# Connectors.net
KiCad netlist of a schematic drawn in Altium Designer
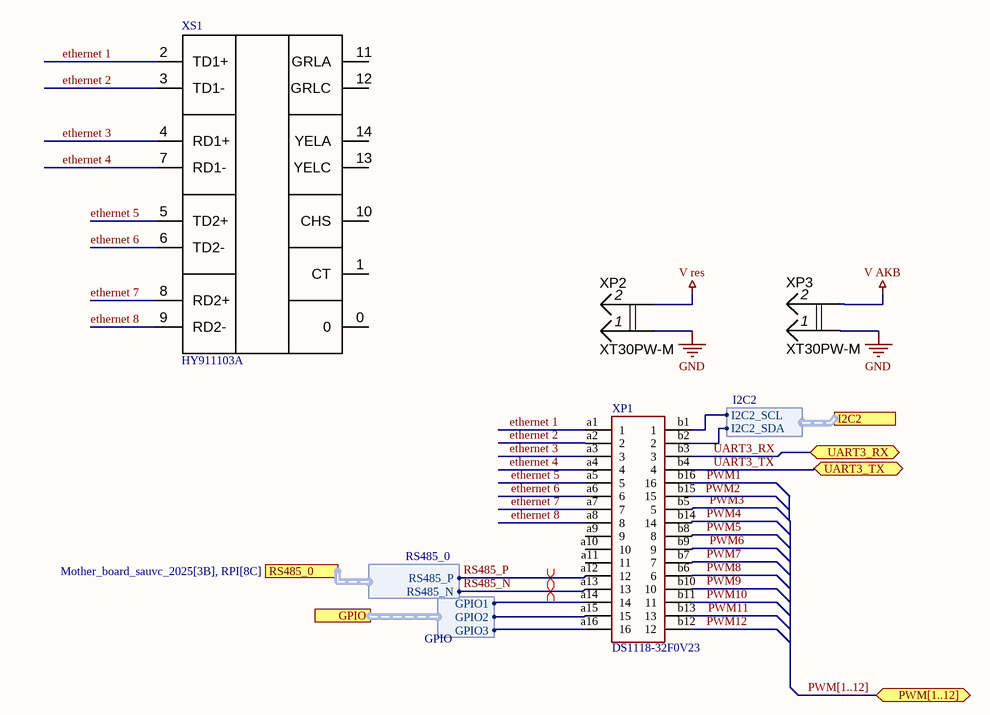
[diagram p0: Connectors.SchDoc]

(export (version "E")
  (design (tool "Eeschema 10.0.6"))
  (components
    (comp (ref "XP1")
      (value "DS1118-32F0V23")
      (footprint "DS1118-32M0R23")
      (libsource (lib "Schliba2") (part "DS1118-32F0V23"))
    )
    (comp (ref "XP2")
      (value "XT30PW-M")
      (footprint "XT30PW-M")
      (fields (field (name "MANUFACTURER") "AMASS") (field (name "PART NUMBER") "XT30PW-M"))
      (libsource (lib "Conectors") (part "XT30PW-M"))
    )
    (comp (ref "XP3")
      (value "XT30PW-M")
      (footprint "XT30PW-M")
      (fields (field (name "MANUFACTURER") "AMASS") (field (name "PART NUMBER") "XT30PW-M"))
      (libsource (lib "Conectors") (part "XT30PW-M"))
    )
    (comp (ref "XS1")
      (value "HY911103A")
      (footprint "HY911103A_HAN")
      (description "RG45")
      (fields (field (name "MANUFACTURER") "HanRun"))
      (libsource (lib "Conectors") (part "HY911103A"))
    )
  )
  (nets
    (net (code "4") (name "/GPIO1") (class "Default")
      (node (ref "XP1") (pin "a14") (pinfunction "14_a14") (pintype "passive"))
    )
    (net (code "5") (name "/GPIO2") (class "Default")
      (node (ref "XP1") (pin "a15") (pinfunction "15_a15") (pintype "passive"))
    )
    (net (code "6") (name "/GPIO3") (class "Default")
      (node (ref "XP1") (pin "a16") (pinfunction "16_a16") (pintype "passive"))
    )
    (net (code "7") (name "/I2C2_SCL") (class "Default")
      (node (ref "XP1") (pin "b1") (pinfunction "1_b1") (pintype "passive"))
    )
    (net (code "8") (name "/I2C2_SDA") (class "Default")
      (node (ref "XP1") (pin "b2") (pinfunction "2_b2") (pintype "passive"))
    )
    (net (code "9") (name "/PWM1") (class "Default")
      (node (ref "XP1") (pin "b16") (pinfunction "16_b16") (pintype "passive"))
    )
    (net (code "10") (name "/PWM2") (class "Default")
      (node (ref "XP1") (pin "b15") (pinfunction "15_b15") (pintype "passive"))
    )
    (net (code "11") (name "/PWM3") (class "Default")
      (node (ref "XP1") (pin "b5") (pinfunction "5_b5") (pintype "passive"))
    )
    (net (code "12") (name "/PWM4") (class "Default")
      (node (ref "XP1") (pin "b14") (pinfunction "14_b14") (pintype "passive"))
    )
    (net (code "13") (name "/PWM5") (class "Default")
      (node (ref "XP1") (pin "b8") (pinfunction "8_b8") (pintype "passive"))
    )
    (net (code "14") (name "/PWM6") (class "Default")
      (node (ref "XP1") (pin "b9") (pinfunction "9_b9") (pintype "passive"))
    )
    (net (code "15") (name "/PWM7") (class "Default")
      (node (ref "XP1") (pin "b7") (pinfunction "7_b7") (pintype "passive"))
    )
    (net (code "16") (name "/PWM8") (class "Default")
      (node (ref "XP1") (pin "b6") (pinfunction "6_b6") (pintype "passive"))
    )
    (net (code "17") (name "/PWM9") (class "Default")
      (node (ref "XP1") (pin "b10") (pinfunction "10_b10") (pintype "passive"))
    )
    (net (code "18") (name "/PWM10") (class "Default")
      (node (ref "XP1") (pin "b11") (pinfunction "11_b11") (pintype "passive"))
    )
    (net (code "19") (name "/PWM11") (class "Default")
      (node (ref "XP1") (pin "b13") (pinfunction "13_b13") (pintype "passive"))
    )
    (net (code "20") (name "/PWM12") (class "Default")
      (node (ref "XP1") (pin "b12") (pinfunction "12_b12") (pintype "passive"))
    )
    (net (code "22") (name "/RS485_N") (class "Default")
      (node (ref "XP1") (pin "a13") (pinfunction "13_a13") (pintype "passive"))
    )
    (net (code "23") (name "/RS485_P") (class "Default")
      (node (ref "XP1") (pin "a12") (pinfunction "12_a12") (pintype "passive"))
    )
    (net (code "24") (name "/UART3_RX") (class "Default")
      (node (ref "XP1") (pin "b3") (pinfunction "3_b3") (pintype "passive"))
    )
    (net (code "25") (name "/UART3_TX") (class "Default")
      (node (ref "XP1") (pin "b4") (pinfunction "4_b4") (pintype "passive"))
    )
    (net (code "26") (name "/ethernet 1") (class "Default")
      (node (ref "XP1") (pin "a1") (pinfunction "1_a1") (pintype "passive"))
      (node (ref "XS1") (pin "2") (pinfunction "TD1+_2") (pintype "passive"))
    )
    (net (code "27") (name "/ethernet 2") (class "Default")
      (node (ref "XP1") (pin "a2") (pinfunction "2_a2") (pintype "passive"))
      (node (ref "XS1") (pin "3") (pinfunction "TD1-_3") (pintype "passive"))
    )
    (net (code "28") (name "/ethernet 3") (class "Default")
      (node (ref "XP1") (pin "a3") (pinfunction "3_a3") (pintype "passive"))
      (node (ref "XS1") (pin "4") (pinfunction "RD1+_4") (pintype "passive"))
    )
    (net (code "29") (name "/ethernet 4") (class "Default")
      (node (ref "XP1") (pin "a4") (pinfunction "4_a4") (pintype "passive"))
      (node (ref "XS1") (pin "7") (pinfunction "RD1-_7") (pintype "passive"))
    )
    (net (code "30") (name "/ethernet 5") (class "Default")
      (node (ref "XP1") (pin "a5") (pinfunction "5_a5") (pintype "passive"))
      (node (ref "XS1") (pin "5") (pinfunction "TD2+_5") (pintype "passive"))
    )
    (net (code "31") (name "/ethernet 6") (class "Default")
      (node (ref "XP1") (pin "a6") (pinfunction "6_a6") (pintype "passive"))
      (node (ref "XS1") (pin "6") (pinfunction "TD2-_6") (pintype "passive"))
    )
    (net (code "32") (name "/ethernet 7") (class "Default")
      (node (ref "XP1") (pin "a7") (pinfunction "7_a7") (pintype "passive"))
      (node (ref "XS1") (pin "8") (pinfunction "RD2+_8") (pintype "passive"))
    )
    (net (code "33") (name "/ethernet 8") (class "Default")
      (node (ref "XP1") (pin "a8") (pinfunction "8_a8") (pintype "passive"))
      (node (ref "XS1") (pin "9") (pinfunction "RD2-_9") (pintype "passive"))
    )
    (net (code "37") (name "GND") (class "Default")
      (node (ref "XP2") (pin "1") (pinfunction "1_1") (pintype "passive"))
      (node (ref "XP3") (pin "1") (pinfunction "1_1") (pintype "passive"))
    )
    (net (code "38") (name "V AKB") (class "Default")
      (node (ref "XP3") (pin "2") (pinfunction "2_2") (pintype "passive"))
    )
    (net (code "39") (name "V res") (class "Default")
      (node (ref "XP2") (pin "2") (pinfunction "2_2") (pintype "passive"))
    )
    (net (code "40") (name "unconnected-(XP1-9-Pada9)") (class "Default")
      (node (ref "XP1") (pin "a9") (pinfunction "9_a9") (pintype "passive"))
    )
    (net (code "41") (name "unconnected-(XP1-10-Pada10)") (class "Default")
      (node (ref "XP1") (pin "a10") (pinfunction "10_a10") (pintype "passive"))
    )
    (net (code "42") (name "unconnected-(XP1-11-Pada11)") (class "Default")
      (node (ref "XP1") (pin "a11") (pinfunction "11_a11") (pintype "passive"))
    )
    (net (code "43") (name "unconnected-(XS1-CHS-Pad10)") (class "Default")
      (node (ref "XS1") (pin "10") (pinfunction "CHS_10") (pintype "passive"))
    )
    (net (code "44") (name "unconnected-(XS1-CT-Pad1)") (class "Default")
      (node (ref "XS1") (pin "1") (pinfunction "CT_1") (pintype "passive"))
    )
    (net (code "45") (name "unconnected-(XS1-GRLA-Pad11)") (class "Default")
      (node (ref "XS1") (pin "11") (pinfunction "GRLA_11") (pintype "passive"))
    )
    (net (code "46") (name "unconnected-(XS1-GRLC-Pad12)") (class "Default")
      (node (ref "XS1") (pin "12") (pinfunction "GRLC_12") (pintype "passive"))
    )
    (net (code "47") (name "unconnected-(XS1-Pad0)") (class "Default")
      (node (ref "XS1") (pin "0") (pinfunction "0_0") (pintype "passive"))
    )
    (net (code "48") (name "unconnected-(XS1-YELA-Pad14)") (class "Default")
      (node (ref "XS1") (pin "14") (pinfunction "YELA_14") (pintype "passive"))
    )
    (net (code "49") (name "unconnected-(XS1-YELC-Pad13)") (class "Default")
      (node (ref "XS1") (pin "13") (pinfunction "YELC_13") (pintype "passive"))
    )
  )
)
